# Input_Buttons.net
KiCad netlist of a schematic drawn in Altium Designer
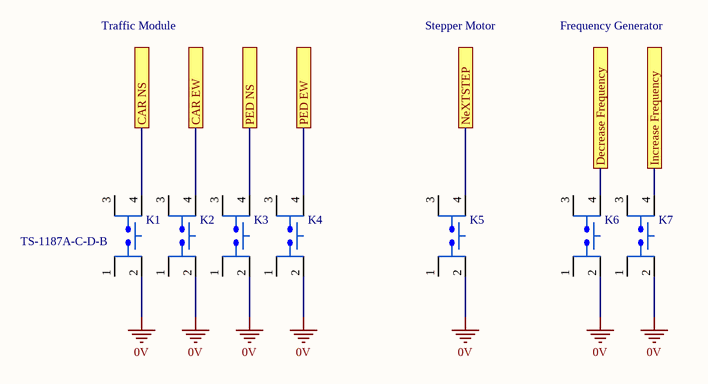
[diagram p0: Input Buttons.SchDoc]

(export (version "E")
  (design (tool "Eeschema 10.0.6"))
  (components
    (comp (ref "K1")
      (value "TS-1187A-C-D-B")
      (footprint "XKB SW-4.5")
      (description "TACTILE SWITCHES SPST 5.10MM X 5.10MM 0.80MM SMD ROHS")
      (fields (field (name "MANUFACTURER") "XKB Enerprise"))
      (libsource (lib "ts_19-standard-library") (part "SPST (Mom) Push Button"))
    )
    (comp (ref "K2")
      (value "TS-1187A-C-D-B")
      (footprint "XKB SW-4.5")
      (description "TACTILE SWITCHES SPST 5.10MM X 5.10MM 0.80MM SMD ROHS")
      (fields (field (name "MANUFACTURER") "XKB Enerprise"))
      (libsource (lib "ts_19-standard-library") (part "SPST (Mom) Push Button"))
    )
    (comp (ref "K3")
      (value "TS-1187A-C-D-B")
      (footprint "XKB SW-4.5")
      (description "TACTILE SWITCHES SPST 5.10MM X 5.10MM 0.80MM SMD ROHS")
      (fields (field (name "MANUFACTURER") "XKB Enerprise"))
      (libsource (lib "ts_19-standard-library") (part "SPST (Mom) Push Button"))
    )
    (comp (ref "K4")
      (value "TS-1187A-C-D-B")
      (footprint "XKB SW-4.5")
      (description "TACTILE SWITCHES SPST 5.10MM X 5.10MM 0.80MM SMD ROHS")
      (fields (field (name "MANUFACTURER") "XKB Enerprise"))
      (libsource (lib "ts_19-standard-library") (part "SPST (Mom) Push Button"))
    )
    (comp (ref "K5")
      (value "TS-1187A-C-D-B")
      (footprint "XKB SW-4.5")
      (description "TACTILE SWITCHES SPST 5.10MM X 5.10MM 0.80MM SMD ROHS")
      (fields (field (name "MANUFACTURER") "XKB Enerprise"))
      (libsource (lib "ts_19-standard-library") (part "SPST (Mom) Push Button"))
    )
    (comp (ref "K6")
      (value "TS-1187A-C-D-B")
      (footprint "XKB SW-4.5")
      (description "TACTILE SWITCHES SPST 5.10MM X 5.10MM 0.80MM SMD ROHS")
      (fields (field (name "MANUFACTURER") "XKB Enerprise"))
      (libsource (lib "ts_19-standard-library") (part "SPST (Mom) Push Button"))
    )
    (comp (ref "K7")
      (value "TS-1187A-C-D-B")
      (footprint "XKB SW-4.5")
      (description "TACTILE SWITCHES SPST 5.10MM X 5.10MM 0.80MM SMD ROHS")
      (fields (field (name "MANUFACTURER") "XKB Enerprise"))
      (libsource (lib "ts_19-standard-library") (part "SPST (Mom) Push Button"))
    )
  )
  (nets
    (net (code "1") (name "/CAR EW") (class "Default")
      (node (ref "K2") (pin "4") (pinfunction "VDD_4") (pintype "passive"))
    )
    (net (code "2") (name "/CAR NS") (class "Default")
      (node (ref "K1") (pin "4") (pinfunction "VDD_4") (pintype "passive"))
    )
    (net (code "3") (name "/Decrease Frequency") (class "Default")
      (node (ref "K6") (pin "4") (pinfunction "VDD_4") (pintype "passive"))
    )
    (net (code "4") (name "/Increase Frequency") (class "Default")
      (node (ref "K7") (pin "4") (pinfunction "VDD_4") (pintype "passive"))
    )
    (net (code "5") (name "/NeXTSTEP") (class "Default")
      (node (ref "K5") (pin "4") (pinfunction "VDD_4") (pintype "passive"))
    )
    (net (code "6") (name "/PED EW") (class "Default")
      (node (ref "K4") (pin "4") (pinfunction "VDD_4") (pintype "passive"))
    )
    (net (code "7") (name "/PED NS") (class "Default")
      (node (ref "K3") (pin "4") (pinfunction "VDD_4") (pintype "passive"))
    )
    (net (code "8") (name "0V") (class "Default")
      (node (ref "K1") (pin "2") (pinfunction "VDD_2") (pintype "passive"))
      (node (ref "K2") (pin "2") (pinfunction "VDD_2") (pintype "passive"))
      (node (ref "K3") (pin "2") (pinfunction "VDD_2") (pintype "passive"))
      (node (ref "K4") (pin "2") (pinfunction "VDD_2") (pintype "passive"))
      (node (ref "K5") (pin "2") (pinfunction "VDD_2") (pintype "passive"))
      (node (ref "K6") (pin "2") (pinfunction "VDD_2") (pintype "passive"))
      (node (ref "K7") (pin "2") (pinfunction "VDD_2") (pintype "passive"))
    )
    (net (code "9") (name "unconnected-(K1-VDD-Pad1)") (class "Default")
      (node (ref "K1") (pin "1") (pinfunction "VDD_1") (pintype "passive"))
    )
    (net (code "10") (name "unconnected-(K1-VDD-Pad3)") (class "Default")
      (node (ref "K1") (pin "3") (pinfunction "VDD_3") (pintype "passive"))
    )
    (net (code "11") (name "unconnected-(K2-VDD-Pad1)") (class "Default")
      (node (ref "K2") (pin "1") (pinfunction "VDD_1") (pintype "passive"))
    )
    (net (code "12") (name "unconnected-(K2-VDD-Pad3)") (class "Default")
      (node (ref "K2") (pin "3") (pinfunction "VDD_3") (pintype "passive"))
    )
    (net (code "13") (name "unconnected-(K3-VDD-Pad1)") (class "Default")
      (node (ref "K3") (pin "1") (pinfunction "VDD_1") (pintype "passive"))
    )
    (net (code "14") (name "unconnected-(K3-VDD-Pad3)") (class "Default")
      (node (ref "K3") (pin "3") (pinfunction "VDD_3") (pintype "passive"))
    )
    (net (code "15") (name "unconnected-(K4-VDD-Pad1)") (class "Default")
      (node (ref "K4") (pin "1") (pinfunction "VDD_1") (pintype "passive"))
    )
    (net (code "16") (name "unconnected-(K4-VDD-Pad3)") (class "Default")
      (node (ref "K4") (pin "3") (pinfunction "VDD_3") (pintype "passive"))
    )
    (net (code "17") (name "unconnected-(K5-VDD-Pad1)") (class "Default")
      (node (ref "K5") (pin "1") (pinfunction "VDD_1") (pintype "passive"))
    )
    (net (code "18") (name "unconnected-(K5-VDD-Pad3)") (class "Default")
      (node (ref "K5") (pin "3") (pinfunction "VDD_3") (pintype "passive"))
    )
    (net (code "19") (name "unconnected-(K6-VDD-Pad1)") (class "Default")
      (node (ref "K6") (pin "1") (pinfunction "VDD_1") (pintype "passive"))
    )
    (net (code "20") (name "unconnected-(K6-VDD-Pad3)") (class "Default")
      (node (ref "K6") (pin "3") (pinfunction "VDD_3") (pintype "passive"))
    )
    (net (code "21") (name "unconnected-(K7-VDD-Pad1)") (class "Default")
      (node (ref "K7") (pin "1") (pinfunction "VDD_1") (pintype "passive"))
    )
    (net (code "22") (name "unconnected-(K7-VDD-Pad3)") (class "Default")
      (node (ref "K7") (pin "3") (pinfunction "VDD_3") (pintype "passive"))
    )
  )
)
